# DualLoopingARFG.net
KiCad netlist of a schematic drawn in EAGLE
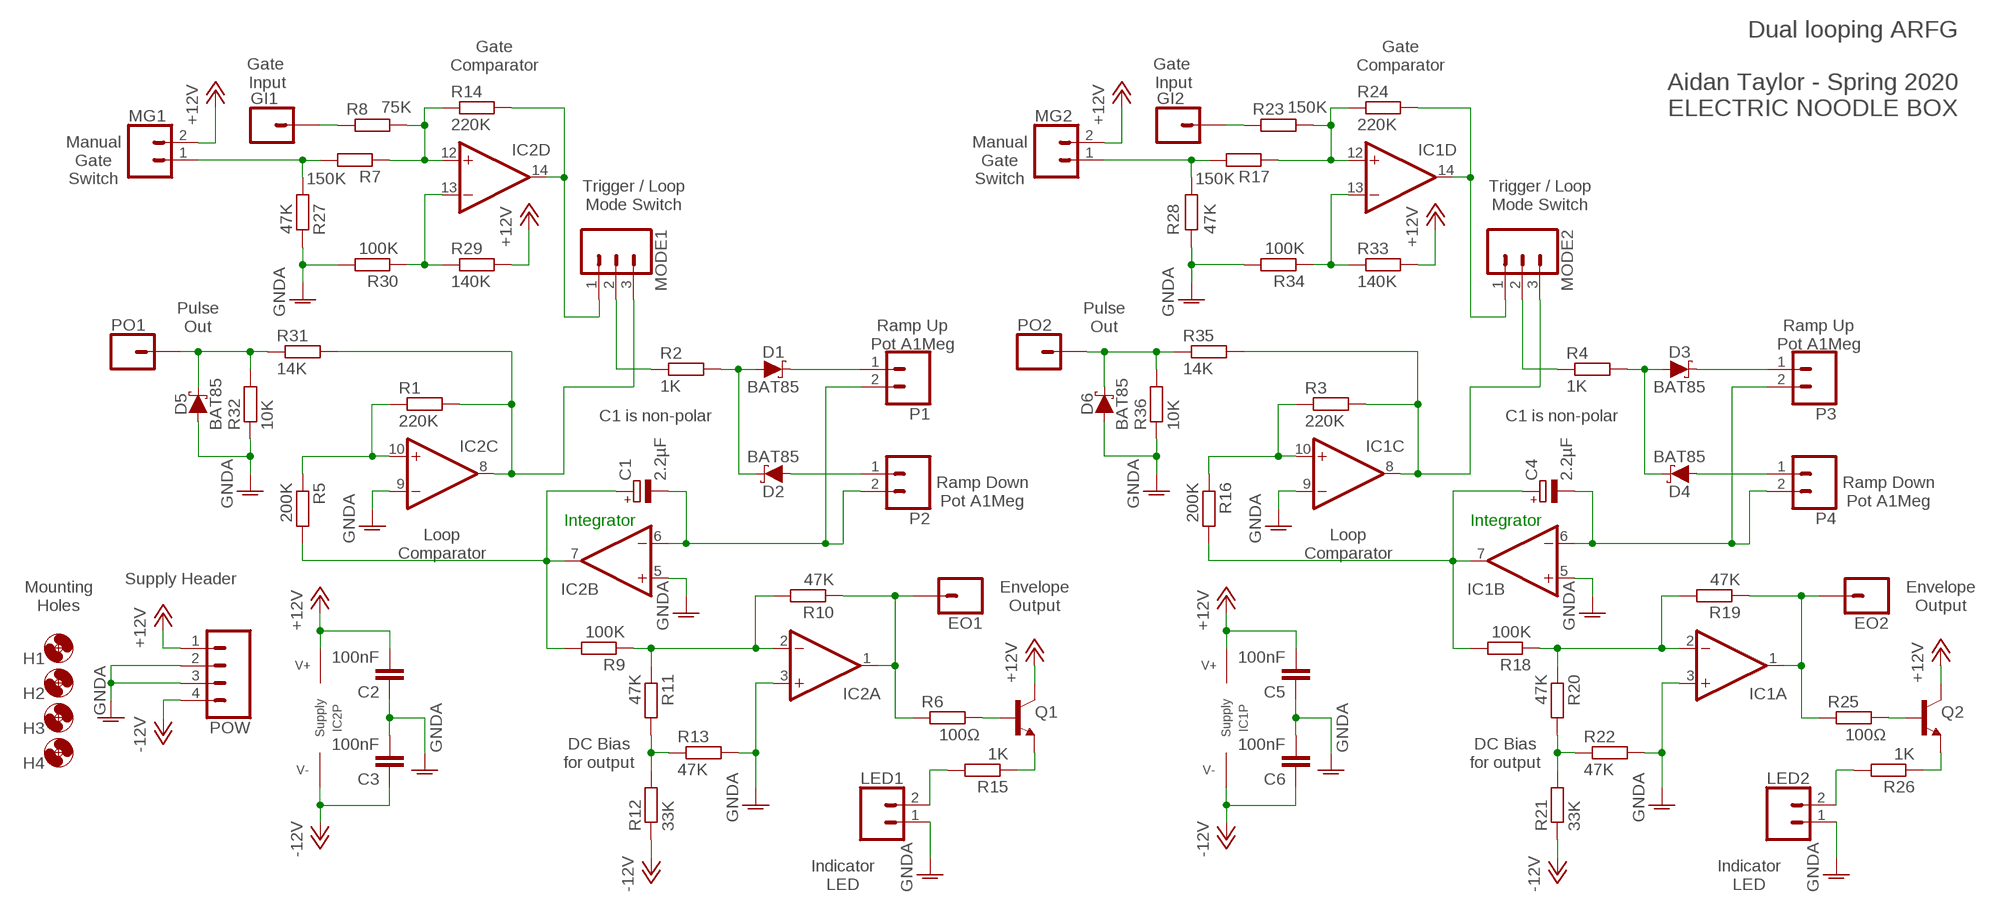
[diagram p0: schematic, sheet 1]

(export (version "E")
  (design (tool "Eeschema 10.0.6"))
  (components
    (comp (ref "C1")
      (value "2.2µF")
      (footprint "eagle-import:E2-5")
      (libsource (lib "eagle-import") (part "CPOL-EUE2-5"))
    )
    (comp (ref "C2")
      (value "100nF")
      (footprint "eagle-import:C050-025X075")
      (libsource (lib "eagle-import") (part "C-EU050-025X075"))
    )
    (comp (ref "C3")
      (value "100nF")
      (footprint "eagle-import:C050-025X075")
      (libsource (lib "eagle-import") (part "C-EU050-025X075"))
    )
    (comp (ref "C4")
      (value "2.2µF")
      (footprint "eagle-import:E2-5")
      (libsource (lib "eagle-import") (part "CPOL-EUE2-5"))
    )
    (comp (ref "C5")
      (value "100nF")
      (footprint "eagle-import:C050-025X075")
      (libsource (lib "eagle-import") (part "C-EU050-025X075"))
    )
    (comp (ref "C6")
      (value "100nF")
      (footprint "eagle-import:C050-025X075")
      (libsource (lib "eagle-import") (part "C-EU050-025X075"))
    )
    (comp (ref "D1")
      (value "BAT85")
      (footprint "eagle-import:DO35-7")
      (libsource (lib "eagle-import") (part "SCHOTTKY_DO35"))
    )
    (comp (ref "D2")
      (value "BAT85")
      (footprint "eagle-import:DO35-7")
      (libsource (lib "eagle-import") (part "SCHOTTKY_DO35"))
    )
    (comp (ref "D3")
      (value "BAT85")
      (footprint "eagle-import:DO35-7")
      (libsource (lib "eagle-import") (part "SCHOTTKY_DO35"))
    )
    (comp (ref "D4")
      (value "BAT85")
      (footprint "eagle-import:DO35-7")
      (libsource (lib "eagle-import") (part "SCHOTTKY_DO35"))
    )
    (comp (ref "D5")
      (value "BAT85")
      (footprint "eagle-import:DO35-7")
      (libsource (lib "eagle-import") (part "SCHOTTKY_DO35"))
    )
    (comp (ref "D6")
      (value "BAT85")
      (footprint "eagle-import:DO35-7")
      (libsource (lib "eagle-import") (part "SCHOTTKY_DO35"))
    )
    (comp (ref "EO1")
      (value "1XWIREPAD")
      (footprint "eagle-import:1X01")
      (libsource (lib "eagle-import") (part "1XWIREPAD"))
    )
    (comp (ref "EO2")
      (value "1XWIREPAD")
      (footprint "eagle-import:1X01")
      (libsource (lib "eagle-import") (part "1XWIREPAD"))
    )
    (comp (ref "GI1")
      (value "1XWIREPAD")
      (footprint "eagle-import:1X01")
      (libsource (lib "eagle-import") (part "1XWIREPAD"))
    )
    (comp (ref "GI2")
      (value "1XWIREPAD")
      (footprint "eagle-import:1X01")
      (libsource (lib "eagle-import") (part "1XWIREPAD"))
    )
    (comp (ref "H1")
      (value "MOUNT-HOLE3.2")
      (footprint "eagle-import:3,2")
      (libsource (lib "eagle-import") (part "MOUNT-HOLE3.2"))
    )
    (comp (ref "H2")
      (value "MOUNT-HOLE3.2")
      (footprint "eagle-import:3,2")
      (libsource (lib "eagle-import") (part "MOUNT-HOLE3.2"))
    )
    (comp (ref "H3")
      (value "MOUNT-HOLE3.2")
      (footprint "eagle-import:3,2")
      (libsource (lib "eagle-import") (part "MOUNT-HOLE3.2"))
    )
    (comp (ref "H4")
      (value "MOUNT-HOLE3.2")
      (footprint "eagle-import:3,2")
      (libsource (lib "eagle-import") (part "MOUNT-HOLE3.2"))
    )
    (comp (ref "IC1")
      (value "TL0X4DIL")
      (footprint "eagle-import:DIL14")
      (libsource (lib "eagle-import") (part "TL0X4DIL"))
    )
    (comp (ref "IC2")
      (value "TL0X4DIL")
      (footprint "eagle-import:DIL14")
      (libsource (lib "eagle-import") (part "TL0X4DIL"))
    )
    (comp (ref "LED1")
      (value "2XWIREPAD")
      (footprint "eagle-import:1X02")
      (libsource (lib "eagle-import") (part "2XWIREPAD"))
    )
    (comp (ref "LED2")
      (value "2XWIREPAD")
      (footprint "eagle-import:1X02")
      (libsource (lib "eagle-import") (part "2XWIREPAD"))
    )
    (comp (ref "MG1")
      (value "2XWIREPAD")
      (footprint "eagle-import:1X02")
      (libsource (lib "eagle-import") (part "2XWIREPAD"))
    )
    (comp (ref "MG2")
      (value "2XWIREPAD")
      (footprint "eagle-import:1X02")
      (libsource (lib "eagle-import") (part "2XWIREPAD"))
    )
    (comp (ref "MODE1")
      (value "3XWIREPAD")
      (footprint "eagle-import:1X03")
      (libsource (lib "eagle-import") (part "3XWIREPAD"))
    )
    (comp (ref "MODE2")
      (value "3XWIREPAD")
      (footprint "eagle-import:1X03")
      (libsource (lib "eagle-import") (part "3XWIREPAD"))
    )
    (comp (ref "P1")
      (value "2XWIREPAD")
      (footprint "eagle-import:1X02")
      (libsource (lib "eagle-import") (part "2XWIREPAD"))
    )
    (comp (ref "P2")
      (value "2XWIREPAD")
      (footprint "eagle-import:1X02")
      (libsource (lib "eagle-import") (part "2XWIREPAD"))
    )
    (comp (ref "P3")
      (value "2XWIREPAD")
      (footprint "eagle-import:1X02")
      (libsource (lib "eagle-import") (part "2XWIREPAD"))
    )
    (comp (ref "P4")
      (value "2XWIREPAD")
      (footprint "eagle-import:1X02")
      (libsource (lib "eagle-import") (part "2XWIREPAD"))
    )
    (comp (ref "PO1")
      (value "1XWIREPAD")
      (footprint "eagle-import:1X01")
      (libsource (lib "eagle-import") (part "1XWIREPAD"))
    )
    (comp (ref "PO2")
      (value "1XWIREPAD")
      (footprint "eagle-import:1X01")
      (libsource (lib "eagle-import") (part "1XWIREPAD"))
    )
    (comp (ref "POW")
      (value "4XMOLEX")
      (footprint "eagle-import:MOLEX-1X4")
      (fields (field (name "SPICEPREFIX") "E"))
      (libsource (lib "eagle-import") (part "4XMOLEX"))
    )
    (comp (ref "Q1")
      (value "2N3904")
      (footprint "eagle-import:TO92")
      (libsource (lib "eagle-import") (part "2N3904"))
    )
    (comp (ref "Q2")
      (value "2N3904")
      (footprint "eagle-import:TO92")
      (libsource (lib "eagle-import") (part "2N3904"))
    )
    (comp (ref "R1")
      (value "220K")
      (footprint "eagle-import:0207_10")
      (libsource (lib "eagle-import") (part "R-EU_0207/10"))
    )
    (comp (ref "R2")
      (value "1K")
      (footprint "eagle-import:0207_10")
      (libsource (lib "eagle-import") (part "R-EU_0207/10"))
    )
    (comp (ref "R3")
      (value "220K")
      (footprint "eagle-import:0207_10")
      (libsource (lib "eagle-import") (part "R-EU_0207/10"))
    )
    (comp (ref "R4")
      (value "1K")
      (footprint "eagle-import:0207_10")
      (libsource (lib "eagle-import") (part "R-EU_0207/10"))
    )
    (comp (ref "R5")
      (value "200K")
      (footprint "eagle-import:0207_10")
      (libsource (lib "eagle-import") (part "R-EU_0207/10"))
    )
    (comp (ref "R6")
      (value "100Ω")
      (footprint "eagle-import:0207_10")
      (libsource (lib "eagle-import") (part "R-EU_0207/10"))
    )
    (comp (ref "R7")
      (value "150K")
      (footprint "eagle-import:0207_10")
      (libsource (lib "eagle-import") (part "R-EU_0207/10"))
    )
    (comp (ref "R8")
      (value "75K")
      (footprint "eagle-import:0207_10")
      (libsource (lib "eagle-import") (part "R-EU_0207/10"))
    )
    (comp (ref "R9")
      (value "100K")
      (footprint "eagle-import:0207_10")
      (libsource (lib "eagle-import") (part "R-EU_0207/10"))
    )
    (comp (ref "R10")
      (value "47K")
      (footprint "eagle-import:0207_10")
      (libsource (lib "eagle-import") (part "R-EU_0207/10"))
    )
    (comp (ref "R11")
      (value "47K")
      (footprint "eagle-import:0207_10")
      (libsource (lib "eagle-import") (part "R-EU_0207/10"))
    )
    (comp (ref "R12")
      (value "33K")
      (footprint "eagle-import:0207_10")
      (libsource (lib "eagle-import") (part "R-EU_0207/10"))
    )
    (comp (ref "R13")
      (value "47K")
      (footprint "eagle-import:0207_10")
      (libsource (lib "eagle-import") (part "R-EU_0207/10"))
    )
    (comp (ref "R14")
      (value "220K")
      (footprint "eagle-import:0207_10")
      (libsource (lib "eagle-import") (part "R-EU_0207/10"))
    )
    (comp (ref "R15")
      (value "1K")
      (footprint "eagle-import:0207_10")
      (libsource (lib "eagle-import") (part "R-EU_0207/10"))
    )
    (comp (ref "R16")
      (value "200K")
      (footprint "eagle-import:0207_10")
      (libsource (lib "eagle-import") (part "R-EU_0207/10"))
    )
    (comp (ref "R17")
      (value "150K")
      (footprint "eagle-import:0207_10")
      (libsource (lib "eagle-import") (part "R-EU_0207/10"))
    )
    (comp (ref "R18")
      (value "100K")
      (footprint "eagle-import:0207_10")
      (libsource (lib "eagle-import") (part "R-EU_0207/10"))
    )
    (comp (ref "R19")
      (value "47K")
      (footprint "eagle-import:0207_10")
      (libsource (lib "eagle-import") (part "R-EU_0207/10"))
    )
    (comp (ref "R20")
      (value "47K")
      (footprint "eagle-import:0207_10")
      (libsource (lib "eagle-import") (part "R-EU_0207/10"))
    )
    (comp (ref "R21")
      (value "33K")
      (footprint "eagle-import:0207_10")
      (libsource (lib "eagle-import") (part "R-EU_0207/10"))
    )
    (comp (ref "R22")
      (value "47K")
      (footprint "eagle-import:0207_10")
      (libsource (lib "eagle-import") (part "R-EU_0207/10"))
    )
    (comp (ref "R23")
      (value "150K")
      (footprint "eagle-import:0207_10")
      (libsource (lib "eagle-import") (part "R-EU_0207/10"))
    )
    (comp (ref "R24")
      (value "220K")
      (footprint "eagle-import:0207_10")
      (libsource (lib "eagle-import") (part "R-EU_0207/10"))
    )
    (comp (ref "R25")
      (value "100Ω")
      (footprint "eagle-import:0207_10")
      (libsource (lib "eagle-import") (part "R-EU_0207/10"))
    )
    (comp (ref "R26")
      (value "1K")
      (footprint "eagle-import:0207_10")
      (libsource (lib "eagle-import") (part "R-EU_0207/10"))
    )
    (comp (ref "R27")
      (value "47K")
      (footprint "eagle-import:0207_10")
      (libsource (lib "eagle-import") (part "R-EU_0207/10"))
    )
    (comp (ref "R28")
      (value "47K")
      (footprint "eagle-import:0207_10")
      (libsource (lib "eagle-import") (part "R-EU_0207/10"))
    )
    (comp (ref "R29")
      (value "140K")
      (footprint "eagle-import:0207_10")
      (libsource (lib "eagle-import") (part "R-EU_0207/10"))
    )
    (comp (ref "R30")
      (value "100K")
      (footprint "eagle-import:0207_10")
      (libsource (lib "eagle-import") (part "R-EU_0207/10"))
    )
    (comp (ref "R31")
      (value "14K")
      (footprint "eagle-import:0207_10")
      (libsource (lib "eagle-import") (part "R-EU_0207/10"))
    )
    (comp (ref "R32")
      (value "10K")
      (footprint "eagle-import:0207_10")
      (libsource (lib "eagle-import") (part "R-EU_0207/10"))
    )
    (comp (ref "R33")
      (value "140K")
      (footprint "eagle-import:0207_10")
      (libsource (lib "eagle-import") (part "R-EU_0207/10"))
    )
    (comp (ref "R34")
      (value "100K")
      (footprint "eagle-import:0207_10")
      (libsource (lib "eagle-import") (part "R-EU_0207/10"))
    )
    (comp (ref "R35")
      (value "14K")
      (footprint "eagle-import:0207_10")
      (libsource (lib "eagle-import") (part "R-EU_0207/10"))
    )
    (comp (ref "R36")
      (value "10K")
      (footprint "eagle-import:0207_10")
      (libsource (lib "eagle-import") (part "R-EU_0207/10"))
    )
  )
  (nets
    (net (code "1") (name "+12V") (class "Default")
      (node (ref "C2") (pin "2") (pinfunction "2_2") (pintype "passive"))
      (node (ref "C5") (pin "2") (pinfunction "2_2") (pintype "passive"))
      (node (ref "IC1") (pin "4") (pinfunction "V+_4") (pintype "bidirectional"))
      (node (ref "IC2") (pin "4") (pinfunction "V+_4") (pintype "bidirectional"))
      (node (ref "MG1") (pin "2") (pinfunction "2_2") (pintype "passive"))
      (node (ref "MG2") (pin "2") (pinfunction "2_2") (pintype "passive"))
      (node (ref "POW") (pin "1") (pinfunction "1_1") (pintype "passive"))
      (node (ref "Q1") (pin "1") (pinfunction "C_1") (pintype "passive"))
      (node (ref "Q2") (pin "1") (pinfunction "C_1") (pintype "passive"))
      (node (ref "R29") (pin "2") (pinfunction "2_2") (pintype "passive"))
      (node (ref "R33") (pin "2") (pinfunction "2_2") (pintype "passive"))
    )
    (net (code "2") (name "-12V") (class "Default")
      (node (ref "C3") (pin "1") (pinfunction "1_1") (pintype "passive"))
      (node (ref "C6") (pin "1") (pinfunction "1_1") (pintype "passive"))
      (node (ref "IC1") (pin "11") (pinfunction "V-_11") (pintype "bidirectional"))
      (node (ref "IC2") (pin "11") (pinfunction "V-_11") (pintype "bidirectional"))
      (node (ref "POW") (pin "4") (pinfunction "4_4") (pintype "passive"))
      (node (ref "R12") (pin "1") (pinfunction "1_1") (pintype "passive"))
      (node (ref "R21") (pin "1") (pinfunction "1_1") (pintype "passive"))
    )
    (net (code "3") (name "GNDA") (class "Default")
      (node (ref "C2") (pin "1") (pinfunction "1_1") (pintype "passive"))
      (node (ref "C3") (pin "2") (pinfunction "2_2") (pintype "passive"))
      (node (ref "C5") (pin "1") (pinfunction "1_1") (pintype "passive"))
      (node (ref "C6") (pin "2") (pinfunction "2_2") (pintype "passive"))
      (node (ref "D5") (pin "A") (pinfunction "A_A") (pintype "passive"))
      (node (ref "D6") (pin "A") (pinfunction "A_A") (pintype "passive"))
      (node (ref "IC1") (pin "3") (pinfunction "+IN_3") (pintype "input"))
      (node (ref "IC1") (pin "5") (pinfunction "+IN_5") (pintype "input"))
      (node (ref "IC1") (pin "9") (pinfunction "-IN_9") (pintype "input"))
      (node (ref "IC2") (pin "3") (pinfunction "+IN_3") (pintype "input"))
      (node (ref "IC2") (pin "5") (pinfunction "+IN_5") (pintype "input"))
      (node (ref "IC2") (pin "9") (pinfunction "-IN_9") (pintype "input"))
      (node (ref "LED1") (pin "1") (pinfunction "1_1") (pintype "passive"))
      (node (ref "LED2") (pin "1") (pinfunction "1_1") (pintype "passive"))
      (node (ref "POW") (pin "2") (pinfunction "2_2") (pintype "passive"))
      (node (ref "POW") (pin "3") (pinfunction "3_3") (pintype "passive"))
      (node (ref "R13") (pin "2") (pinfunction "2_2") (pintype "passive"))
      (node (ref "R22") (pin "2") (pinfunction "2_2") (pintype "passive"))
      (node (ref "R27") (pin "2") (pinfunction "2_2") (pintype "passive"))
      (node (ref "R28") (pin "2") (pinfunction "2_2") (pintype "passive"))
      (node (ref "R30") (pin "2") (pinfunction "2_2") (pintype "passive"))
      (node (ref "R32") (pin "1") (pinfunction "1_1") (pintype "passive"))
      (node (ref "R34") (pin "2") (pinfunction "2_2") (pintype "passive"))
      (node (ref "R36") (pin "1") (pinfunction "1_1") (pintype "passive"))
    )
    (net (code "4") (name "Net-(D1-PadA)") (class "Default")
      (node (ref "D1") (pin "A") (pinfunction "A_A") (pintype "passive"))
      (node (ref "D2") (pin "C") (pinfunction "C_C") (pintype "passive"))
      (node (ref "R2") (pin "2") (pinfunction "2_2") (pintype "passive"))
    )
    (net (code "5") (name "Net-(D1-PadC)") (class "Default")
      (node (ref "D1") (pin "C") (pinfunction "C_C") (pintype "passive"))
      (node (ref "P1") (pin "1") (pinfunction "1_1") (pintype "passive"))
    )
    (net (code "6") (name "Net-(D2-PadA)") (class "Default")
      (node (ref "D2") (pin "A") (pinfunction "A_A") (pintype "passive"))
      (node (ref "P2") (pin "1") (pinfunction "1_1") (pintype "passive"))
    )
    (net (code "7") (name "Net-(D3-PadA)") (class "Default")
      (node (ref "D3") (pin "A") (pinfunction "A_A") (pintype "passive"))
      (node (ref "D4") (pin "C") (pinfunction "C_C") (pintype "passive"))
      (node (ref "R4") (pin "2") (pinfunction "2_2") (pintype "passive"))
    )
    (net (code "8") (name "Net-(D3-PadC)") (class "Default")
      (node (ref "D3") (pin "C") (pinfunction "C_C") (pintype "passive"))
      (node (ref "P3") (pin "1") (pinfunction "1_1") (pintype "passive"))
    )
    (net (code "9") (name "Net-(D4-PadA)") (class "Default")
      (node (ref "D4") (pin "A") (pinfunction "A_A") (pintype "passive"))
      (node (ref "P4") (pin "1") (pinfunction "1_1") (pintype "passive"))
    )
    (net (code "10") (name "Net-(D5-PadC)") (class "Default")
      (node (ref "D5") (pin "C") (pinfunction "C_C") (pintype "passive"))
      (node (ref "PO1") (pin "1") (pinfunction "1_1") (pintype "passive"))
      (node (ref "R31") (pin "1") (pinfunction "1_1") (pintype "passive"))
      (node (ref "R32") (pin "2") (pinfunction "2_2") (pintype "passive"))
    )
    (net (code "11") (name "Net-(D6-PadC)") (class "Default")
      (node (ref "D6") (pin "C") (pinfunction "C_C") (pintype "passive"))
      (node (ref "PO2") (pin "1") (pinfunction "1_1") (pintype "passive"))
      (node (ref "R35") (pin "1") (pinfunction "1_1") (pintype "passive"))
      (node (ref "R36") (pin "2") (pinfunction "2_2") (pintype "passive"))
    )
    (net (code "12") (name "Net-(GI1-Pad1)") (class "Default")
      (node (ref "GI1") (pin "1") (pinfunction "1_1") (pintype "passive"))
      (node (ref "R8") (pin "1") (pinfunction "1_1") (pintype "passive"))
    )
    (net (code "13") (name "Net-(GI2-Pad1)") (class "Default")
      (node (ref "GI2") (pin "1") (pinfunction "1_1") (pintype "passive"))
      (node (ref "R23") (pin "1") (pinfunction "1_1") (pintype "passive"))
    )
    (net (code "14") (name "Net-(IC1A--IN)") (class "Default")
      (node (ref "IC1") (pin "2") (pinfunction "-IN_2") (pintype "input"))
      (node (ref "R18") (pin "1") (pinfunction "1_1") (pintype "passive"))
      (node (ref "R19") (pin "2") (pinfunction "2_2") (pintype "passive"))
      (node (ref "R20") (pin "1") (pinfunction "1_1") (pintype "passive"))
    )
    (net (code "15") (name "Net-(IC1A-OUT)") (class "Default")
      (node (ref "EO2") (pin "1") (pinfunction "1_1") (pintype "passive"))
      (node (ref "IC1") (pin "1") (pinfunction "OUT_1") (pintype "output"))
      (node (ref "R19") (pin "1") (pinfunction "1_1") (pintype "passive"))
      (node (ref "R25") (pin "1") (pinfunction "1_1") (pintype "passive"))
    )
    (net (code "16") (name "Net-(IC1B--IN)") (class "Default")
      (node (ref "C4") (pin "-") (pinfunction "-_-") (pintype "passive"))
      (node (ref "IC1") (pin "6") (pinfunction "-IN_6") (pintype "input"))
      (node (ref "P3") (pin "2") (pinfunction "2_2") (pintype "passive"))
      (node (ref "P4") (pin "2") (pinfunction "2_2") (pintype "passive"))
    )
    (net (code "17") (name "Net-(IC1B-OUT)") (class "Default")
      (node (ref "C4") (pin "+") (pinfunction "+_+") (pintype "passive"))
      (node (ref "IC1") (pin "7") (pinfunction "OUT_7") (pintype "output"))
      (node (ref "R16") (pin "2") (pinfunction "2_2") (pintype "passive"))
      (node (ref "R18") (pin "2") (pinfunction "2_2") (pintype "passive"))
    )
    (net (code "18") (name "Net-(IC1C-+IN)") (class "Default")
      (node (ref "IC1") (pin "10") (pinfunction "+IN_10") (pintype "input"))
      (node (ref "R16") (pin "1") (pinfunction "1_1") (pintype "passive"))
      (node (ref "R3") (pin "1") (pinfunction "1_1") (pintype "passive"))
    )
    (net (code "19") (name "Net-(IC1C-OUT)") (class "Default")
      (node (ref "IC1") (pin "8") (pinfunction "OUT_8") (pintype "output"))
      (node (ref "MODE2") (pin "3") (pinfunction "3_3") (pintype "passive"))
      (node (ref "R3") (pin "2") (pinfunction "2_2") (pintype "passive"))
      (node (ref "R35") (pin "2") (pinfunction "2_2") (pintype "passive"))
    )
    (net (code "20") (name "Net-(IC1D-+IN)") (class "Default")
      (node (ref "IC1") (pin "12") (pinfunction "+IN_12") (pintype "input"))
      (node (ref "R17") (pin "1") (pinfunction "1_1") (pintype "passive"))
      (node (ref "R23") (pin "2") (pinfunction "2_2") (pintype "passive"))
      (node (ref "R24") (pin "1") (pinfunction "1_1") (pintype "passive"))
    )
    (net (code "21") (name "Net-(IC1D--IN)") (class "Default")
      (node (ref "IC1") (pin "13") (pinfunction "-IN_13") (pintype "input"))
      (node (ref "R33") (pin "1") (pinfunction "1_1") (pintype "passive"))
      (node (ref "R34") (pin "1") (pinfunction "1_1") (pintype "passive"))
    )
    (net (code "22") (name "Net-(IC1D-OUT)") (class "Default")
      (node (ref "IC1") (pin "14") (pinfunction "OUT_14") (pintype "output"))
      (node (ref "MODE2") (pin "1") (pinfunction "1_1") (pintype "passive"))
      (node (ref "R24") (pin "2") (pinfunction "2_2") (pintype "passive"))
    )
    (net (code "23") (name "Net-(IC2A--IN)") (class "Default")
      (node (ref "IC2") (pin "2") (pinfunction "-IN_2") (pintype "input"))
      (node (ref "R10") (pin "2") (pinfunction "2_2") (pintype "passive"))
      (node (ref "R11") (pin "1") (pinfunction "1_1") (pintype "passive"))
      (node (ref "R9") (pin "1") (pinfunction "1_1") (pintype "passive"))
    )
    (net (code "24") (name "Net-(IC2A-OUT)") (class "Default")
      (node (ref "EO1") (pin "1") (pinfunction "1_1") (pintype "passive"))
      (node (ref "IC2") (pin "1") (pinfunction "OUT_1") (pintype "output"))
      (node (ref "R10") (pin "1") (pinfunction "1_1") (pintype "passive"))
      (node (ref "R6") (pin "1") (pinfunction "1_1") (pintype "passive"))
    )
    (net (code "25") (name "Net-(IC2B--IN)") (class "Default")
      (node (ref "C1") (pin "-") (pinfunction "-_-") (pintype "passive"))
      (node (ref "IC2") (pin "6") (pinfunction "-IN_6") (pintype "input"))
      (node (ref "P1") (pin "2") (pinfunction "2_2") (pintype "passive"))
      (node (ref "P2") (pin "2") (pinfunction "2_2") (pintype "passive"))
    )
    (net (code "26") (name "Net-(IC2B-OUT)") (class "Default")
      (node (ref "C1") (pin "+") (pinfunction "+_+") (pintype "passive"))
      (node (ref "IC2") (pin "7") (pinfunction "OUT_7") (pintype "output"))
      (node (ref "R5") (pin "2") (pinfunction "2_2") (pintype "passive"))
      (node (ref "R9") (pin "2") (pinfunction "2_2") (pintype "passive"))
    )
    (net (code "27") (name "Net-(IC2C-+IN)") (class "Default")
      (node (ref "IC2") (pin "10") (pinfunction "+IN_10") (pintype "input"))
      (node (ref "R1") (pin "1") (pinfunction "1_1") (pintype "passive"))
      (node (ref "R5") (pin "1") (pinfunction "1_1") (pintype "passive"))
    )
    (net (code "28") (name "Net-(IC2C-OUT)") (class "Default")
      (node (ref "IC2") (pin "8") (pinfunction "OUT_8") (pintype "output"))
      (node (ref "MODE1") (pin "3") (pinfunction "3_3") (pintype "passive"))
      (node (ref "R1") (pin "2") (pinfunction "2_2") (pintype "passive"))
      (node (ref "R31") (pin "2") (pinfunction "2_2") (pintype "passive"))
    )
    (net (code "29") (name "Net-(IC2D-+IN)") (class "Default")
      (node (ref "IC2") (pin "12") (pinfunction "+IN_12") (pintype "input"))
      (node (ref "R14") (pin "1") (pinfunction "1_1") (pintype "passive"))
      (node (ref "R7") (pin "1") (pinfunction "1_1") (pintype "passive"))
      (node (ref "R8") (pin "2") (pinfunction "2_2") (pintype "passive"))
    )
    (net (code "30") (name "Net-(IC2D--IN)") (class "Default")
      (node (ref "IC2") (pin "13") (pinfunction "-IN_13") (pintype "input"))
      (node (ref "R29") (pin "1") (pinfunction "1_1") (pintype "passive"))
      (node (ref "R30") (pin "1") (pinfunction "1_1") (pintype "passive"))
    )
    (net (code "31") (name "Net-(IC2D-OUT)") (class "Default")
      (node (ref "IC2") (pin "14") (pinfunction "OUT_14") (pintype "output"))
      (node (ref "MODE1") (pin "1") (pinfunction "1_1") (pintype "passive"))
      (node (ref "R14") (pin "2") (pinfunction "2_2") (pintype "passive"))
    )
    (net (code "32") (name "Net-(LED1-Pad2)") (class "Default")
      (node (ref "LED1") (pin "2") (pinfunction "2_2") (pintype "passive"))
      (node (ref "R15") (pin "2") (pinfunction "2_2") (pintype "passive"))
    )
    (net (code "33") (name "Net-(LED2-Pad2)") (class "Default")
      (node (ref "LED2") (pin "2") (pinfunction "2_2") (pintype "passive"))
      (node (ref "R26") (pin "2") (pinfunction "2_2") (pintype "passive"))
    )
    (net (code "34") (name "Net-(MG1-Pad1)") (class "Default")
      (node (ref "MG1") (pin "1") (pinfunction "1_1") (pintype "passive"))
      (node (ref "R27") (pin "1") (pinfunction "1_1") (pintype "passive"))
      (node (ref "R7") (pin "2") (pinfunction "2_2") (pintype "passive"))
    )
    (net (code "35") (name "Net-(MG2-Pad1)") (class "Default")
      (node (ref "MG2") (pin "1") (pinfunction "1_1") (pintype "passive"))
      (node (ref "R17") (pin "2") (pinfunction "2_2") (pintype "passive"))
      (node (ref "R28") (pin "1") (pinfunction "1_1") (pintype "passive"))
    )
    (net (code "36") (name "Net-(MODE1-Pad2)") (class "Default")
      (node (ref "MODE1") (pin "2") (pinfunction "2_2") (pintype "passive"))
      (node (ref "R2") (pin "1") (pinfunction "1_1") (pintype "passive"))
    )
    (net (code "37") (name "Net-(MODE2-Pad2)") (class "Default")
      (node (ref "MODE2") (pin "2") (pinfunction "2_2") (pintype "passive"))
      (node (ref "R4") (pin "1") (pinfunction "1_1") (pintype "passive"))
    )
    (net (code "38") (name "Net-(Q1-B)") (class "Default")
      (node (ref "Q1") (pin "2") (pinfunction "B_2") (pintype "passive"))
      (node (ref "R6") (pin "2") (pinfunction "2_2") (pintype "passive"))
    )
    (net (code "39") (name "Net-(Q1-E)") (class "Default")
      (node (ref "Q1") (pin "3") (pinfunction "E_3") (pintype "passive"))
      (node (ref "R15") (pin "1") (pinfunction "1_1") (pintype "passive"))
    )
    (net (code "40") (name "Net-(Q2-B)") (class "Default")
      (node (ref "Q2") (pin "2") (pinfunction "B_2") (pintype "passive"))
      (node (ref "R25") (pin "2") (pinfunction "2_2") (pintype "passive"))
    )
    (net (code "41") (name "Net-(Q2-E)") (class "Default")
      (node (ref "Q2") (pin "3") (pinfunction "E_3") (pintype "passive"))
      (node (ref "R26") (pin "1") (pinfunction "1_1") (pintype "passive"))
    )
    (net (code "42") (name "Net-(R11-Pad2)") (class "Default")
      (node (ref "R11") (pin "2") (pinfunction "2_2") (pintype "passive"))
      (node (ref "R12") (pin "2") (pinfunction "2_2") (pintype "passive"))
      (node (ref "R13") (pin "1") (pinfunction "1_1") (pintype "passive"))
    )
    (net (code "43") (name "Net-(R20-Pad2)") (class "Default")
      (node (ref "R20") (pin "2") (pinfunction "2_2") (pintype "passive"))
      (node (ref "R21") (pin "2") (pinfunction "2_2") (pintype "passive"))
      (node (ref "R22") (pin "1") (pinfunction "1_1") (pintype "passive"))
    )
  )
)
